# Driver_Relay_SPDT.net
KiCad netlist of a schematic drawn in Altium Designer
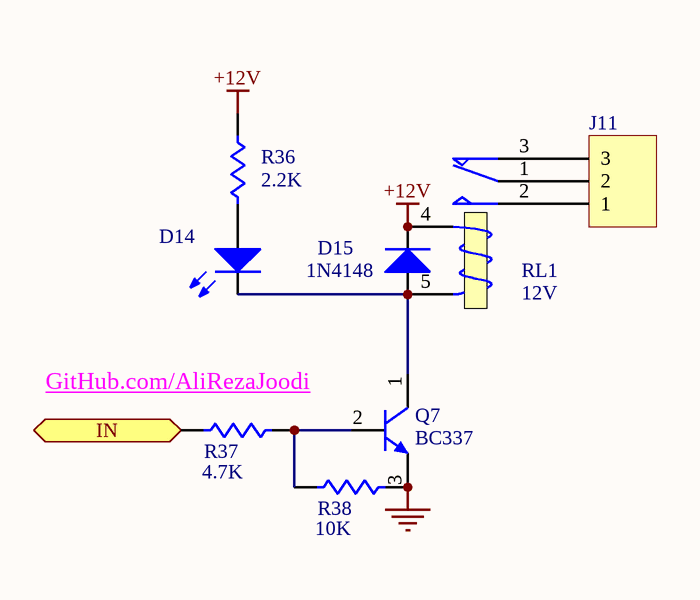
[diagram p0: Driver_Relay_SPDT.SchDoc]

(export (version "E")
  (design (tool "Eeschema 10.0.6"))
  (components
    (comp (ref "D14")
      (value "LED")
      (footprint "LED-5mm_Red")
      (description "Typical INFRARED GaAs LED")
      (fields (field (name "MANUFACTURER") "Generic Components") (field (name "PUBLISHER") "Altium Limited"))
      (libsource (lib "Miscellaneous Devices") (part "LED"))
    )
    (comp (ref "D15")
      (value "1N4148")
      (footprint "DIODE-0.4")
      (description "Default Diode")
      (fields
        (field (name "MANUFACTURER") "Generic Components")
        (field (name "Comment") "Diode")
        (field (name "PUBLISHER") "Altium Limited")
      )
      (libsource (lib "Miscellaneous Devices") (part "Diode"))
    )
    (comp (ref "J11")
      (value "Header 3")
      (footprint "Fonics_3PIN_1")
      (description "Header, 3-Pin")
      (fields (field (name "PUBLISHER") "Altium Limited"))
      (libsource (lib "Miscellaneous Connectors") (part "Header 3"))
    )
    (comp (ref "Q7")
      (value "BC337")
      (footprint "TO92C")
      (description "NPN Bipolar Transistor")
      (fields
        (field (name "MANUFACTURER") "Generic Components")
        (field (name "Comment") "NPN")
        (field (name "PUBLISHER") "Altium Limited")
      )
      (libsource (lib "Miscellaneous Devices") (part "NPN"))
    )
    (comp (ref "R36")
      (value "2.2K")
      (footprint "AXIAL-0.4")
      (description "Resistor")
      (fields (field (name "MANUFACTURER") "Generic Components") (field (name "PUBLISHER") "Altium Limited"))
      (libsource (lib "Miscellaneous Devices") (part "Res1"))
    )
    (comp (ref "R37")
      (value "4.7K")
      (footprint "AXIAL-0.4")
      (description "Resistor")
      (fields (field (name "MANUFACTURER") "Generic Components") (field (name "PUBLISHER") "Altium Limited"))
      (libsource (lib "Miscellaneous Devices") (part "Res1"))
    )
    (comp (ref "R38")
      (value "10K")
      (footprint "AXIAL-0.4")
      (description "Resistor")
      (fields (field (name "MANUFACTURER") "Generic Components") (field (name "PUBLISHER") "Altium Limited"))
      (libsource (lib "Miscellaneous Devices") (part "Res1"))
    )
    (comp (ref "RL1")
      (value "12V")
      (footprint "RELAY-SPDT-1")
      (description "SPDT Relay")
      (fields
        (field (name "MANUFACTURER") "Generic Components")
        (field (name "Comment") "RL1")
        (field (name "PUBLISHER") "Altium Limited")
      )
      (libsource (lib "Miscellaneous Devices") (part "Relay-SPDT_2"))
    )
  )
  (nets
    (net (code "1") (name "+12V") (class "Default")
      (node (ref "D15") (pin "2") (pinfunction "K_2") (pintype "passive"))
      (node (ref "R36") (pin "1") (pinfunction "1_1") (pintype "passive"))
      (node (ref "RL1") (pin "4") (pinfunction "T1_4") (pintype "passive"))
    )
    (net (code "2") (name "/IN") (class "Default")
      (node (ref "R37") (pin "2") (pinfunction "2_2") (pintype "passive"))
    )
    (net (code "3") (name "GND") (class "Default")
      (node (ref "Q7") (pin "3") (pinfunction "E_3") (pintype "passive"))
      (node (ref "R38") (pin "1") (pinfunction "1_1") (pintype "passive"))
    )
    (net (code "4") (name "Net-(D14-A)") (class "Default")
      (node (ref "D14") (pin "1") (pinfunction "A_1") (pintype "passive"))
      (node (ref "R36") (pin "2") (pinfunction "2_2") (pintype "passive"))
    )
    (net (code "5") (name "Net-(D14-K)") (class "Default")
      (node (ref "D14") (pin "2") (pinfunction "K_2") (pintype "passive"))
      (node (ref "D15") (pin "1") (pinfunction "A_1") (pintype "passive"))
      (node (ref "Q7") (pin "1") (pinfunction "C_1") (pintype "passive"))
      (node (ref "RL1") (pin "5") (pinfunction "T2_5") (pintype "passive"))
    )
    (net (code "6") (name "Net-(Q7-B)") (class "Default")
      (node (ref "Q7") (pin "2") (pinfunction "B_2") (pintype "passive"))
      (node (ref "R37") (pin "1") (pinfunction "1_1") (pintype "passive"))
      (node (ref "R38") (pin "2") (pinfunction "2_2") (pintype "passive"))
    )
    (net (code "7") (name "Net-(RL1-COM)") (class "Default")
      (node (ref "J11") (pin "2") (pinfunction "2_2") (pintype "passive"))
      (node (ref "RL1") (pin "1") (pinfunction "COM_1") (pintype "passive"))
    )
    (net (code "8") (name "Net-(RL1-NC)") (class "Default")
      (node (ref "J11") (pin "3") (pinfunction "3_3") (pintype "passive"))
      (node (ref "RL1") (pin "3") (pinfunction "NC_3") (pintype "passive"))
    )
    (net (code "9") (name "Net-(RL1-NO)") (class "Default")
      (node (ref "J11") (pin "1") (pinfunction "1_1") (pintype "passive"))
      (node (ref "RL1") (pin "2") (pinfunction "NO_2") (pintype "passive"))
    )
  )
)
